# microSD_Shield.net
KiCad netlist of a schematic drawn in EAGLE
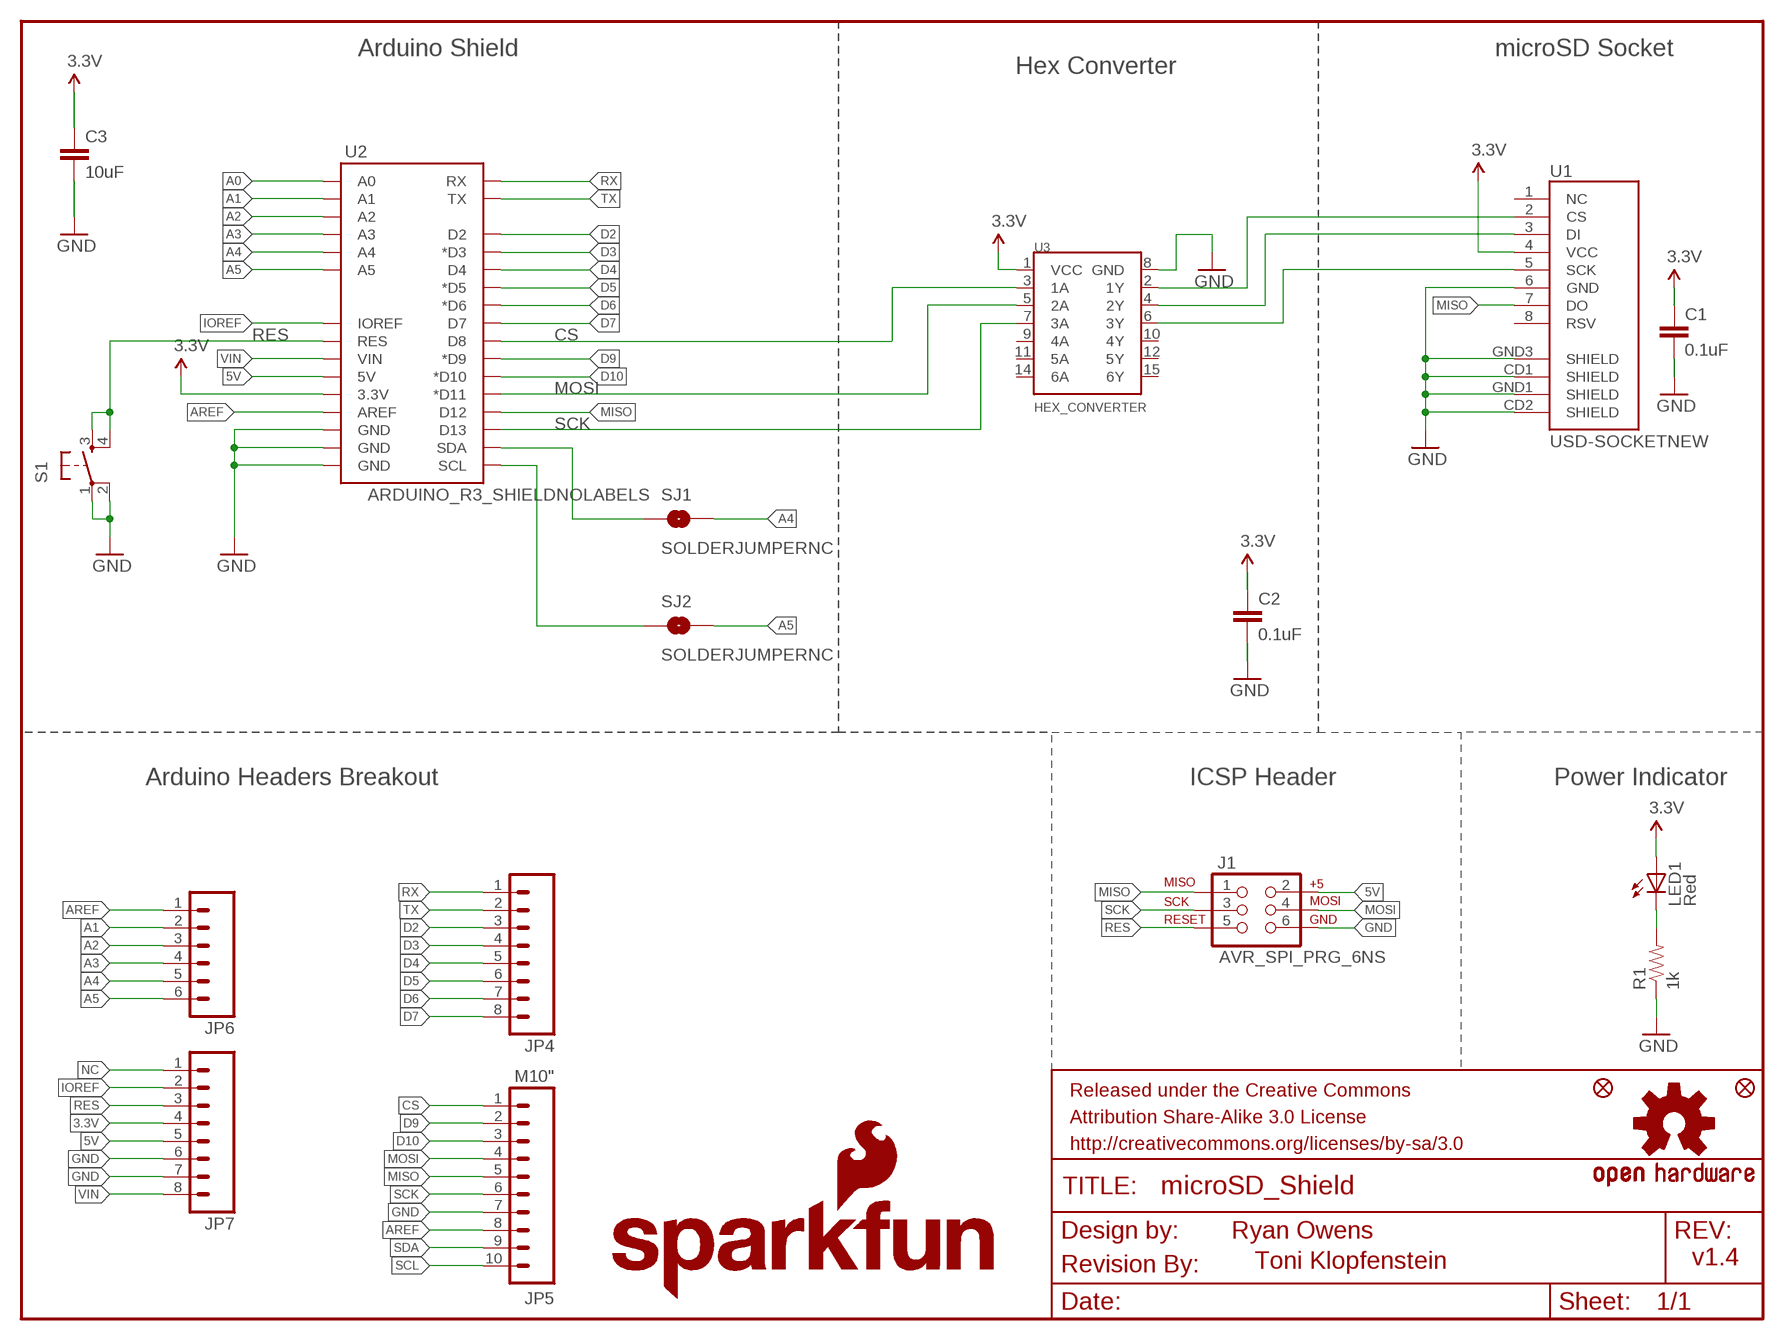
[diagram p0: schematic, sheet 1]

(export (version "E")
  (design (tool "Eeschema 10.0.6"))
  (components
    (comp (ref "C1")
      (value "0.1uF")
      (footprint "eagle-import:0603-CAP")
      (libsource (lib "eagle-import") (part "0.1UF-25V-5%(0603)"))
    )
    (comp (ref "C2")
      (value "0.1uF")
      (footprint "eagle-import:0603-CAP")
      (libsource (lib "eagle-import") (part "0.1UF-25V-5%(0603)"))
    )
    (comp (ref "C3")
      (value "10uF")
      (footprint "eagle-import:0603-CAP")
      (libsource (lib "eagle-import") (part "10UF-6.3V-20%(0603)"))
    )
    (comp (ref "FRAME1")
      (value "FRAME-LETTER")
      (footprint "eagle-import:CREATIVE_COMMONS")
      (libsource (lib "eagle-import") (part "FRAME-LETTER"))
    )
    (comp (ref "J1")
      (value "AVR_SPI_PRG_6NS")
      (footprint "eagle-import:2X3-NS")
      (libsource (lib "eagle-import") (part "AVR_SPI_PRG_6NS"))
    )
    (comp (ref "JP1")
      (value "SFE_LOGO_NAME_FLAME.1_INCH")
      (footprint "eagle-import:SFE_LOGO_NAME_FLAME_.1")
      (libsource (lib "eagle-import") (part "SFE_LOGO_NAME_FLAME.1_INCH"))
    )
    (comp (ref "JP2")
      (value "FIDUCIAL1X2")
      (footprint "eagle-import:FIDUCIAL-1X2")
      (libsource (lib "eagle-import") (part "FIDUCIAL1X2"))
    )
    (comp (ref "JP3")
      (value "FIDUCIAL1X2")
      (footprint "eagle-import:FIDUCIAL-1X2")
      (libsource (lib "eagle-import") (part "FIDUCIAL1X2"))
    )
    (comp (ref "JP4")
      (value "M08")
      (footprint "eagle-import:1X08")
      (libsource (lib "eagle-import") (part "M08"))
    )
    (comp (ref "JP5")
      (value "M10\"")
      (footprint "eagle-import:1X10")
      (libsource (lib "eagle-import") (part "M10{dblquote}"))
    )
    (comp (ref "JP6")
      (value "M06SIP")
      (footprint "eagle-import:1X06")
      (libsource (lib "eagle-import") (part "M06SIP"))
    )
    (comp (ref "JP7")
      (value "M081X08")
      (footprint "eagle-import:1X08")
      (libsource (lib "eagle-import") (part "M081X08"))
    )
    (comp (ref "LED1")
      (value "Red")
      (footprint "eagle-import:LED-0603")
      (libsource (lib "eagle-import") (part "LED0603"))
    )
    (comp (ref "LOGO1")
      (value "OSHW-LOGOM")
      (footprint "eagle-import:OSHW-LOGO-M")
      (libsource (lib "eagle-import") (part "OSHW-LOGOM"))
    )
    (comp (ref "LOGO2")
      (value "SFE_LOGO_FLAME.6_INCH")
      (footprint "eagle-import:SFE_LOGO_FLAME_.6")
      (libsource (lib "eagle-import") (part "SFE_LOGO_FLAME.6_INCH"))
    )
    (comp (ref "R1")
      (value "1k")
      (footprint "eagle-import:0603-RES")
      (libsource (lib "eagle-import") (part "RESISTOR0603-RES"))
    )
    (comp (ref "S1")
      (value "TAC_SWITCHSMD")
      (footprint "eagle-import:TACTILE_SWITCH_SMD")
      (libsource (lib "eagle-import") (part "TAC_SWITCHSMD"))
    )
    (comp (ref "SJ1")
      (value "SOLDERJUMPERNC")
      (footprint "eagle-import:SJ_2S")
      (libsource (lib "eagle-import") (part "SOLDERJUMPERNC"))
    )
    (comp (ref "SJ2")
      (value "SOLDERJUMPERNC")
      (footprint "eagle-import:SJ_2S")
      (libsource (lib "eagle-import") (part "SOLDERJUMPERNC"))
    )
    (comp (ref "U$1")
      (value "REVISION")
      (footprint "eagle-import:REVISION")
      (libsource (lib "eagle-import") (part "REVISION"))
    )
    (comp (ref "U1")
      (value "USD-SOCKETNEW")
      (footprint "eagle-import:MICRO-SD-SOCKET-PP")
      (libsource (lib "eagle-import") (part "USD-SOCKETNEW"))
    )
    (comp (ref "U2")
      (value "ARDUINO_R3_SHIELDNOLABELS")
      (footprint "eagle-import:UNO_R3_SHIELD_NOLABELS")
      (libsource (lib "eagle-import") (part "ARDUINO_R3_SHIELDNOLABELS"))
    )
    (comp (ref "U3")
      (value "HEX_CONVERTER")
      (footprint "eagle-import:SO016")
      (libsource (lib "eagle-import") (part "HEX_CONVERTER"))
    )
  )
  (nets
    (net (code "1") (name "3.3V") (class "Default")
      (node (ref "C1") (pin "1") (pinfunction "1_1") (pintype "passive"))
      (node (ref "C2") (pin "1") (pinfunction "1_1") (pintype "passive"))
      (node (ref "C3") (pin "1") (pinfunction "1_1") (pintype "passive"))
      (node (ref "JP7") (pin "4") (pinfunction "4_4") (pintype "passive"))
      (node (ref "LED1") (pin "A") (pinfunction "A_A") (pintype "passive"))
      (node (ref "U1") (pin "4") (pinfunction "VCC_4") (pintype "bidirectional"))
      (node (ref "U2") (pin "3.3V") (pinfunction "3.3V_3.3V") (pintype "bidirectional"))
      (node (ref "U3") (pin "1") (pinfunction "VCC_1") (pintype "bidirectional"))
    )
    (net (code "2") (name "5V") (class "Default")
      (node (ref "J1") (pin "2") (pinfunction "2_2") (pintype "passive"))
      (node (ref "JP7") (pin "5") (pinfunction "5_5") (pintype "passive"))
      (node (ref "U2") (pin "5V") (pinfunction "5V_5V") (pintype "bidirectional"))
    )
    (net (code "3") (name "A0") (class "Default")
      (node (ref "JP6") (pin "1") (pinfunction "1_1") (pintype "passive"))
      (node (ref "U2") (pin "A0") (pinfunction "A0_A0") (pintype "bidirectional"))
    )
    (net (code "4") (name "A1") (class "Default")
      (node (ref "JP6") (pin "2") (pinfunction "2_2") (pintype "passive"))
      (node (ref "U2") (pin "A1") (pinfunction "A1_A1") (pintype "bidirectional"))
    )
    (net (code "5") (name "A2") (class "Default")
      (node (ref "JP6") (pin "3") (pinfunction "3_3") (pintype "passive"))
      (node (ref "U2") (pin "A2") (pinfunction "A2_A2") (pintype "bidirectional"))
    )
    (net (code "6") (name "A3") (class "Default")
      (node (ref "JP6") (pin "4") (pinfunction "4_4") (pintype "passive"))
      (node (ref "U2") (pin "A3") (pinfunction "A3_A3") (pintype "bidirectional"))
    )
    (net (code "7") (name "A4") (class "Default")
      (node (ref "JP6") (pin "5") (pinfunction "5_5") (pintype "passive"))
      (node (ref "SJ1") (pin "2") (pinfunction "2_2") (pintype "passive"))
      (node (ref "U2") (pin "A4") (pinfunction "A4_A4") (pintype "bidirectional"))
    )
    (net (code "8") (name "A5") (class "Default")
      (node (ref "JP6") (pin "6") (pinfunction "6_6") (pintype "passive"))
      (node (ref "SJ2") (pin "2") (pinfunction "2_2") (pintype "passive"))
      (node (ref "U2") (pin "A5") (pinfunction "A5_A5") (pintype "bidirectional"))
    )
    (net (code "9") (name "AREF") (class "Default")
      (node (ref "JP5") (pin "8") (pinfunction "8_8") (pintype "passive"))
      (node (ref "U2") (pin "AREF") (pinfunction "AREF_AREF") (pintype "bidirectional"))
    )
    (net (code "10") (name "CS") (class "Default")
      (node (ref "JP5") (pin "1") (pinfunction "1_1") (pintype "passive"))
      (node (ref "U2") (pin "D8") (pinfunction "D8_D8") (pintype "bidirectional"))
      (node (ref "U3") (pin "3") (pinfunction "1A_3") (pintype "bidirectional"))
    )
    (net (code "11") (name "D2") (class "Default")
      (node (ref "JP4") (pin "3") (pinfunction "3_3") (pintype "passive"))
      (node (ref "U2") (pin "D2") (pinfunction "D2_D2") (pintype "bidirectional"))
    )
    (net (code "12") (name "D3") (class "Default")
      (node (ref "JP4") (pin "4") (pinfunction "4_4") (pintype "passive"))
      (node (ref "U2") (pin "D3") (pinfunction "*D3_D3") (pintype "bidirectional"))
    )
    (net (code "13") (name "D4") (class "Default")
      (node (ref "JP4") (pin "5") (pinfunction "5_5") (pintype "passive"))
      (node (ref "U2") (pin "D4") (pinfunction "D4_D4") (pintype "bidirectional"))
    )
    (net (code "14") (name "D5") (class "Default")
      (node (ref "JP4") (pin "6") (pinfunction "6_6") (pintype "passive"))
      (node (ref "U2") (pin "D5") (pinfunction "*D5_D5") (pintype "bidirectional"))
    )
    (net (code "15") (name "D6") (class "Default")
      (node (ref "JP4") (pin "7") (pinfunction "7_7") (pintype "passive"))
      (node (ref "U2") (pin "D6") (pinfunction "*D6_D6") (pintype "bidirectional"))
    )
    (net (code "16") (name "D7") (class "Default")
      (node (ref "JP4") (pin "8") (pinfunction "8_8") (pintype "passive"))
      (node (ref "U2") (pin "D7") (pinfunction "D7_D7") (pintype "bidirectional"))
    )
    (net (code "17") (name "D9") (class "Default")
      (node (ref "JP5") (pin "2") (pinfunction "2_2") (pintype "passive"))
      (node (ref "U2") (pin "D9") (pinfunction "*D9_D9") (pintype "bidirectional"))
    )
    (net (code "18") (name "D10") (class "Default")
      (node (ref "JP5") (pin "3") (pinfunction "3_3") (pintype "passive"))
      (node (ref "U2") (pin "D10") (pinfunction "*D10_D10") (pintype "bidirectional"))
    )
    (net (code "19") (name "GND") (class "Default")
      (node (ref "C1") (pin "2") (pinfunction "2_2") (pintype "passive"))
      (node (ref "C2") (pin "2") (pinfunction "2_2") (pintype "passive"))
      (node (ref "C3") (pin "2") (pinfunction "2_2") (pintype "passive"))
      (node (ref "J1") (pin "6") (pinfunction "6_6") (pintype "passive"))
      (node (ref "JP5") (pin "7") (pinfunction "7_7") (pintype "passive"))
      (node (ref "JP7") (pin "6") (pinfunction "6_6") (pintype "passive"))
      (node (ref "JP7") (pin "7") (pinfunction "7_7") (pintype "passive"))
      (node (ref "R1") (pin "1") (pinfunction "1_1") (pintype "passive"))
      (node (ref "S1") (pin "1") (pinfunction "1_1") (pintype "passive"))
      (node (ref "S1") (pin "2") (pinfunction "2_2") (pintype "passive"))
      (node (ref "U1") (pin "6") (pinfunction "GND_6") (pintype "bidirectional"))
      (node (ref "U1") (pin "CD1") (pinfunction "SHIELD_CD1") (pintype "bidirectional"))
      (node (ref "U1") (pin "CD2") (pinfunction "SHIELD_CD2") (pintype "bidirectional"))
      (node (ref "U1") (pin "GND1") (pinfunction "SHIELD_GND1") (pintype "bidirectional"))
      (node (ref "U1") (pin "GND3") (pinfunction "SHIELD_GND3") (pintype "bidirectional"))
      (node (ref "U2") (pin "GND@0") (pinfunction "GND_GND@0") (pintype "bidirectional"))
      (node (ref "U2") (pin "GND@1") (pinfunction "GND_GND@1") (pintype "bidirectional"))
      (node (ref "U2") (pin "GND@2") (pinfunction "GND_GND@2") (pintype "bidirectional"))
      (node (ref "U3") (pin "8") (pinfunction "GND_8") (pintype "bidirectional"))
    )
    (net (code "20") (name "IOREF") (class "Default")
      (node (ref "JP7") (pin "2") (pinfunction "2_2") (pintype "passive"))
      (node (ref "U2") (pin "IOREF") (pinfunction "IOREF_IOREF") (pintype "bidirectional"))
    )
    (net (code "21") (name "MISO") (class "Default")
      (node (ref "J1") (pin "1") (pinfunction "1_1") (pintype "passive"))
      (node (ref "JP5") (pin "5") (pinfunction "5_5") (pintype "passive"))
      (node (ref "U1") (pin "7") (pinfunction "DO_7") (pintype "bidirectional"))
      (node (ref "U2") (pin "D12") (pinfunction "D12_D12") (pintype "bidirectional"))
    )
    (net (code "22") (name "MOSI") (class "Default")
      (node (ref "J1") (pin "4") (pinfunction "4_4") (pintype "passive"))
      (node (ref "JP5") (pin "4") (pinfunction "4_4") (pintype "passive"))
      (node (ref "U2") (pin "D11") (pinfunction "*D11_D11") (pintype "bidirectional"))
      (node (ref "U3") (pin "5") (pinfunction "2A_5") (pintype "bidirectional"))
    )
    (net (code "23") (name "NC") (class "Default")
      (node (ref "JP7") (pin "1") (pinfunction "1_1") (pintype "passive"))
    )
    (net (code "24") (name "Net-(LED1-PadC)") (class "Default")
      (node (ref "LED1") (pin "C") (pinfunction "C_C") (pintype "passive"))
      (node (ref "R1") (pin "2") (pinfunction "2_2") (pintype "passive"))
    )
    (net (code "25") (name "Net-(U1-CS)") (class "Default")
      (node (ref "U1") (pin "2") (pinfunction "CS_2") (pintype "bidirectional"))
      (node (ref "U3") (pin "2") (pinfunction "1Y_2") (pintype "bidirectional"))
    )
    (net (code "26") (name "Net-(U1-DI)") (class "Default")
      (node (ref "U1") (pin "3") (pinfunction "DI_3") (pintype "bidirectional"))
      (node (ref "U3") (pin "4") (pinfunction "2Y_4") (pintype "bidirectional"))
    )
    (net (code "27") (name "Net-(U1-SCK)") (class "Default")
      (node (ref "U1") (pin "5") (pinfunction "SCK_5") (pintype "bidirectional"))
      (node (ref "U3") (pin "6") (pinfunction "3Y_6") (pintype "bidirectional"))
    )
    (net (code "28") (name "RES") (class "Default")
      (node (ref "J1") (pin "5") (pinfunction "5_5") (pintype "passive"))
      (node (ref "JP7") (pin "3") (pinfunction "3_3") (pintype "passive"))
      (node (ref "S1") (pin "3") (pinfunction "3_3") (pintype "passive"))
      (node (ref "S1") (pin "4") (pinfunction "4_4") (pintype "passive"))
      (node (ref "U2") (pin "RES") (pinfunction "RES_RES") (pintype "bidirectional"))
    )
    (net (code "29") (name "RX") (class "Default")
      (node (ref "JP4") (pin "1") (pinfunction "1_1") (pintype "passive"))
      (node (ref "U2") (pin "RX") (pinfunction "RX_RX") (pintype "bidirectional"))
    )
    (net (code "30") (name "SCK") (class "Default")
      (node (ref "J1") (pin "3") (pinfunction "3_3") (pintype "passive"))
      (node (ref "JP5") (pin "6") (pinfunction "6_6") (pintype "passive"))
      (node (ref "U2") (pin "D13") (pinfunction "D13_D13") (pintype "bidirectional"))
      (node (ref "U3") (pin "7") (pinfunction "3A_7") (pintype "bidirectional"))
    )
    (net (code "31") (name "SCL") (class "Default")
      (node (ref "JP5") (pin "10") (pinfunction "10_10") (pintype "passive"))
      (node (ref "SJ2") (pin "1") (pinfunction "1_1") (pintype "passive"))
      (node (ref "U2") (pin "SCL") (pinfunction "SCL_SCL") (pintype "bidirectional"))
    )
    (net (code "32") (name "SDA") (class "Default")
      (node (ref "JP5") (pin "9") (pinfunction "9_9") (pintype "passive"))
      (node (ref "SJ1") (pin "1") (pinfunction "1_1") (pintype "passive"))
      (node (ref "U2") (pin "SDA") (pinfunction "SDA_SDA") (pintype "bidirectional"))
    )
    (net (code "33") (name "TX") (class "Default")
      (node (ref "JP4") (pin "2") (pinfunction "2_2") (pintype "passive"))
      (node (ref "U2") (pin "TX") (pinfunction "TX_TX") (pintype "bidirectional"))
    )
    (net (code "34") (name "VIN") (class "Default")
      (node (ref "JP7") (pin "8") (pinfunction "8_8") (pintype "passive"))
      (node (ref "U2") (pin "VIN") (pinfunction "VIN_VIN") (pintype "bidirectional"))
    )
    (net (code "35") (name "unconnected-(U1-NC-Pad1)") (class "Default")
      (node (ref "U1") (pin "1") (pinfunction "NC_1") (pintype "bidirectional"))
    )
    (net (code "36") (name "unconnected-(U1-RSV-Pad8)") (class "Default")
      (node (ref "U1") (pin "8") (pinfunction "RSV_8") (pintype "bidirectional"))
    )
    (net (code "37") (name "unconnected-(U3-4A-Pad9)") (class "Default")
      (node (ref "U3") (pin "9") (pinfunction "4A_9") (pintype "bidirectional"))
    )
    (net (code "38") (name "unconnected-(U3-4Y-Pad10)") (class "Default")
      (node (ref "U3") (pin "10") (pinfunction "4Y_10") (pintype "bidirectional"))
    )
    (net (code "39") (name "unconnected-(U3-5A-Pad11)") (class "Default")
      (node (ref "U3") (pin "11") (pinfunction "5A_11") (pintype "bidirectional"))
    )
    (net (code "40") (name "unconnected-(U3-5Y-Pad12)") (class "Default")
      (node (ref "U3") (pin "12") (pinfunction "5Y_12") (pintype "bidirectional"))
    )
    (net (code "41") (name "unconnected-(U3-6A-Pad14)") (class "Default")
      (node (ref "U3") (pin "14") (pinfunction "6A_14") (pintype "bidirectional"))
    )
    (net (code "42") (name "unconnected-(U3-6Y-Pad15)") (class "Default")
      (node (ref "U3") (pin "15") (pinfunction "6Y_15") (pintype "bidirectional"))
    )
  )
)
